# Blinkenlights.net
KiCad netlist of a schematic drawn in EAGLE
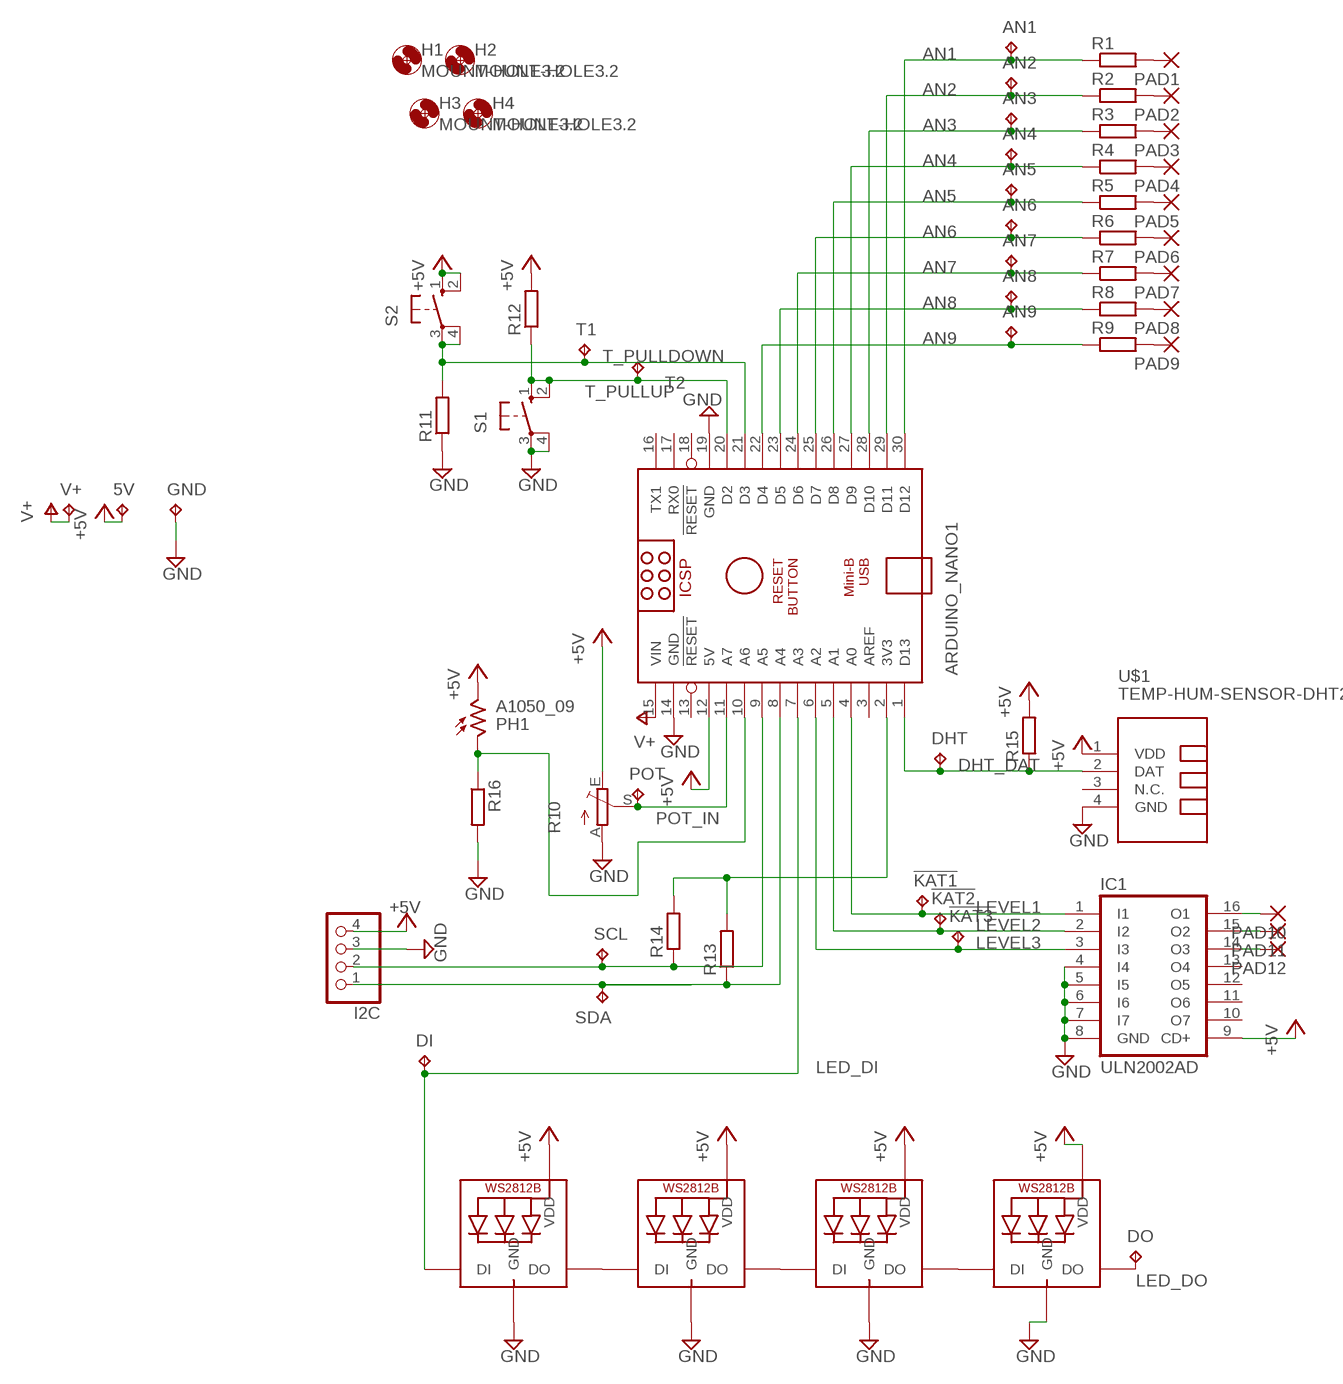
[diagram p0: schematic, sheet 1]

(export (version "E")
  (design (tool "Eeschema 10.0.6"))
  (components
    (comp (ref "!KAT1")
      (value "TPB1,27")
      (footprint "eagle-import:B1,27")
      (libsource (lib "eagle-import") (part "TPB1,27"))
    )
    (comp (ref "!KAT2")
      (value "TPB1,27")
      (footprint "eagle-import:B1,27")
      (libsource (lib "eagle-import") (part "TPB1,27"))
    )
    (comp (ref "!KAT3")
      (value "TPB1,27")
      (footprint "eagle-import:B1,27")
      (libsource (lib "eagle-import") (part "TPB1,27"))
    )
    (comp (ref "5V")
      (value "TPPAD1-17")
      (footprint "eagle-import:P1-17")
      (libsource (lib "eagle-import") (part "TPPAD1-17"))
    )
    (comp (ref "AN1")
      (value "TPB1,27")
      (footprint "eagle-import:B1,27")
      (libsource (lib "eagle-import") (part "TPB1,27"))
    )
    (comp (ref "AN2")
      (value "TPB1,27")
      (footprint "eagle-import:B1,27")
      (libsource (lib "eagle-import") (part "TPB1,27"))
    )
    (comp (ref "AN3")
      (value "TPB1,27")
      (footprint "eagle-import:B1,27")
      (libsource (lib "eagle-import") (part "TPB1,27"))
    )
    (comp (ref "AN4")
      (value "TPB1,27")
      (footprint "eagle-import:B1,27")
      (libsource (lib "eagle-import") (part "TPB1,27"))
    )
    (comp (ref "AN5")
      (value "TPB1,27")
      (footprint "eagle-import:B1,27")
      (libsource (lib "eagle-import") (part "TPB1,27"))
    )
    (comp (ref "AN6")
      (value "TPB1,27")
      (footprint "eagle-import:B1,27")
      (libsource (lib "eagle-import") (part "TPB1,27"))
    )
    (comp (ref "AN7")
      (value "TPB1,27")
      (footprint "eagle-import:B1,27")
      (libsource (lib "eagle-import") (part "TPB1,27"))
    )
    (comp (ref "AN8")
      (value "TPB1,27")
      (footprint "eagle-import:B1,27")
      (libsource (lib "eagle-import") (part "TPB1,27"))
    )
    (comp (ref "AN9")
      (value "TPB1,27")
      (footprint "eagle-import:B1,27")
      (libsource (lib "eagle-import") (part "TPB1,27"))
    )
    (comp (ref "ARDUINO_NANO1")
      (value "ARDUINO_NANO")
      (footprint "eagle-import:ARDUINO_NANO")
      (libsource (lib "eagle-import") (part "ARDUINO_NANO"))
    )
    (comp (ref "DHT")
      (value "TPB1,27")
      (footprint "eagle-import:B1,27")
      (libsource (lib "eagle-import") (part "TPB1,27"))
    )
    (comp (ref "DI")
      (value "TPB1,27")
      (footprint "eagle-import:B1,27")
      (libsource (lib "eagle-import") (part "TPB1,27"))
    )
    (comp (ref "DO")
      (value "TPB1,27")
      (footprint "eagle-import:B1,27")
      (libsource (lib "eagle-import") (part "TPB1,27"))
    )
    (comp (ref "GND")
      (value "TPPAD1-17")
      (footprint "eagle-import:P1-17")
      (libsource (lib "eagle-import") (part "TPPAD1-17"))
    )
    (comp (ref "H1")
      (value "MOUNT-HOLE3.2")
      (footprint "eagle-import:3,2")
      (libsource (lib "eagle-import") (part "MOUNT-HOLE3.2"))
    )
    (comp (ref "H2")
      (value "MOUNT-HOLE3.2")
      (footprint "eagle-import:3,2")
      (libsource (lib "eagle-import") (part "MOUNT-HOLE3.2"))
    )
    (comp (ref "H3")
      (value "MOUNT-HOLE3.2")
      (footprint "eagle-import:3,2")
      (libsource (lib "eagle-import") (part "MOUNT-HOLE3.2"))
    )
    (comp (ref "H4")
      (value "MOUNT-HOLE3.2")
      (footprint "eagle-import:3,2")
      (libsource (lib "eagle-import") (part "MOUNT-HOLE3.2"))
    )
    (comp (ref "I2C")
      (value "PINHD-1X4")
      (footprint "eagle-import:1X04")
      (libsource (lib "eagle-import") (part "PINHD-1X4"))
    )
    (comp (ref "IC1")
      (value "ULN2002AD")
      (footprint "eagle-import:SO16")
      (libsource (lib "eagle-import") (part "ULN2002AD"))
    )
    (comp (ref "LED1")
      (value "WS2812B5050")
      (footprint "eagle-import:WS2812B")
      (libsource (lib "eagle-import") (part "WS2812B5050"))
    )
    (comp (ref "LED2")
      (value "WS2812B5050")
      (footprint "eagle-import:WS2812B")
      (libsource (lib "eagle-import") (part "WS2812B5050"))
    )
    (comp (ref "LED3")
      (value "WS2812B5050")
      (footprint "eagle-import:WS2812B")
      (libsource (lib "eagle-import") (part "WS2812B5050"))
    )
    (comp (ref "LED4")
      (value "WS2812B5050")
      (footprint "eagle-import:WS2812B")
      (libsource (lib "eagle-import") (part "WS2812B5050"))
    )
    (comp (ref "PAD1")
      (value "2,54/1,1")
      (footprint "eagle-import:2,54_1,1")
      (libsource (lib "eagle-import") (part "2,54/1,1"))
    )
    (comp (ref "PAD2")
      (value "2,54/1,1")
      (footprint "eagle-import:2,54_1,1")
      (libsource (lib "eagle-import") (part "2,54/1,1"))
    )
    (comp (ref "PAD3")
      (value "2,54/1,1")
      (footprint "eagle-import:2,54_1,1")
      (libsource (lib "eagle-import") (part "2,54/1,1"))
    )
    (comp (ref "PAD4")
      (value "2,54/1,1")
      (footprint "eagle-import:2,54_1,1")
      (libsource (lib "eagle-import") (part "2,54/1,1"))
    )
    (comp (ref "PAD5")
      (value "2,54/1,1")
      (footprint "eagle-import:2,54_1,1")
      (libsource (lib "eagle-import") (part "2,54/1,1"))
    )
    (comp (ref "PAD6")
      (value "2,54/1,1")
      (footprint "eagle-import:2,54_1,1")
      (libsource (lib "eagle-import") (part "2,54/1,1"))
    )
    (comp (ref "PAD7")
      (value "2,54/1,1")
      (footprint "eagle-import:2,54_1,1")
      (libsource (lib "eagle-import") (part "2,54/1,1"))
    )
    (comp (ref "PAD8")
      (value "2,54/1,1")
      (footprint "eagle-import:2,54_1,1")
      (libsource (lib "eagle-import") (part "2,54/1,1"))
    )
    (comp (ref "PAD9")
      (value "2,54/1,1")
      (footprint "eagle-import:2,54_1,1")
      (libsource (lib "eagle-import") (part "2,54/1,1"))
    )
    (comp (ref "PAD10")
      (value "2,54/1,1")
      (footprint "eagle-import:2,54_1,1")
      (libsource (lib "eagle-import") (part "2,54/1,1"))
    )
    (comp (ref "PAD11")
      (value "2,54/1,1")
      (footprint "eagle-import:2,54_1,1")
      (libsource (lib "eagle-import") (part "2,54/1,1"))
    )
    (comp (ref "PAD12")
      (value "2,54/1,1")
      (footprint "eagle-import:2,54_1,1")
      (libsource (lib "eagle-import") (part "2,54/1,1"))
    )
    (comp (ref "PH1")
      (value "A1050_09")
      (footprint "eagle-import:T0-46-A10XX")
      (libsource (lib "eagle-import") (part "A1050_09"))
    )
    (comp (ref "POT")
      (value "TPB1,27")
      (footprint "eagle-import:B1,27")
      (libsource (lib "eagle-import") (part "TPB1,27"))
    )
    (comp (ref "R1")
      (value "R-EU_R0603")
      (footprint "eagle-import:R0603")
      (libsource (lib "eagle-import") (part "R-EU_R0603"))
    )
    (comp (ref "R2")
      (value "R-EU_R0603")
      (footprint "eagle-import:R0603")
      (libsource (lib "eagle-import") (part "R-EU_R0603"))
    )
    (comp (ref "R3")
      (value "R-EU_R0603")
      (footprint "eagle-import:R0603")
      (libsource (lib "eagle-import") (part "R-EU_R0603"))
    )
    (comp (ref "R4")
      (value "R-EU_R0603")
      (footprint "eagle-import:R0603")
      (libsource (lib "eagle-import") (part "R-EU_R0603"))
    )
    (comp (ref "R5")
      (value "R-EU_R0603")
      (footprint "eagle-import:R0603")
      (libsource (lib "eagle-import") (part "R-EU_R0603"))
    )
    (comp (ref "R6")
      (value "R-EU_R0603")
      (footprint "eagle-import:R0603")
      (libsource (lib "eagle-import") (part "R-EU_R0603"))
    )
    (comp (ref "R7")
      (value "R-EU_R0603")
      (footprint "eagle-import:R0603")
      (libsource (lib "eagle-import") (part "R-EU_R0603"))
    )
    (comp (ref "R8")
      (value "R-EU_R0603")
      (footprint "eagle-import:R0603")
      (libsource (lib "eagle-import") (part "R-EU_R0603"))
    )
    (comp (ref "R9")
      (value "R-EU_R0603")
      (footprint "eagle-import:R0603")
      (libsource (lib "eagle-import") (part "R-EU_R0603"))
    )
    (comp (ref "R10")
      (value "TRIM_EU-RJ9W")
      (footprint "eagle-import:RJ9W")
      (libsource (lib "eagle-import") (part "TRIM_EU-RJ9W"))
    )
    (comp (ref "R11")
      (value "R-EU_R0805")
      (footprint "eagle-import:R0805")
      (libsource (lib "eagle-import") (part "R-EU_R0805"))
    )
    (comp (ref "R12")
      (value "R-EU_R0805")
      (footprint "eagle-import:R0805")
      (libsource (lib "eagle-import") (part "R-EU_R0805"))
    )
    (comp (ref "R13")
      (value "R-EU_R0805")
      (footprint "eagle-import:R0805")
      (libsource (lib "eagle-import") (part "R-EU_R0805"))
    )
    (comp (ref "R14")
      (value "R-EU_R0805")
      (footprint "eagle-import:R0805")
      (libsource (lib "eagle-import") (part "R-EU_R0805"))
    )
    (comp (ref "R15")
      (value "R-EU_R0805")
      (footprint "eagle-import:R0805")
      (libsource (lib "eagle-import") (part "R-EU_R0805"))
    )
    (comp (ref "R16")
      (value "R-EU_R0805")
      (footprint "eagle-import:R0805")
      (libsource (lib "eagle-import") (part "R-EU_R0805"))
    )
    (comp (ref "S1")
      (value "10-XX")
      (footprint "eagle-import:B3F-10XX")
      (fields (field (name "MPN") "B3F-1000"))
      (libsource (lib "eagle-import") (part "10-XX"))
    )
    (comp (ref "S2")
      (value "10-XX")
      (footprint "eagle-import:B3F-10XX")
      (fields (field (name "MPN") "B3F-1000"))
      (libsource (lib "eagle-import") (part "10-XX"))
    )
    (comp (ref "SCL")
      (value "TPB1,27")
      (footprint "eagle-import:B1,27")
      (libsource (lib "eagle-import") (part "TPB1,27"))
    )
    (comp (ref "SDA")
      (value "TPB1,27")
      (footprint "eagle-import:B1,27")
      (libsource (lib "eagle-import") (part "TPB1,27"))
    )
    (comp (ref "T1")
      (value "TPB1,27")
      (footprint "eagle-import:B1,27")
      (libsource (lib "eagle-import") (part "TPB1,27"))
    )
    (comp (ref "T2")
      (value "TPB1,27")
      (footprint "eagle-import:B1,27")
      (libsource (lib "eagle-import") (part "TPB1,27"))
    )
    (comp (ref "U$1")
      (value "TEMP-HUM-SENSOR-DHT22")
      (footprint "eagle-import:TEMP-HUM-SENSOR-DHT22")
      (libsource (lib "eagle-import") (part "TEMP-HUM-SENSOR-DHT22"))
    )
    (comp (ref "V+")
      (value "TPPAD1-17")
      (footprint "eagle-import:P1-17")
      (libsource (lib "eagle-import") (part "TPPAD1-17"))
    )
  )
  (nets
    (net (code "1") (name "+5V") (class "Default")
      (node (ref "5V") (pin "TP") (pinfunction "TP_TP") (pintype "input"))
      (node (ref "ARDUINO_NANO1") (pin "12") (pinfunction "5V_12") (pintype "power_in"))
      (node (ref "I2C") (pin "4") (pinfunction "4_4") (pintype "passive"))
      (node (ref "IC1") (pin "9") (pinfunction "CD+_9") (pintype "passive"))
      (node (ref "LED1") (pin "1-VDD") (pinfunction "VDD_1-VDD") (pintype "power_in"))
      (node (ref "LED2") (pin "1-VDD") (pinfunction "VDD_1-VDD") (pintype "power_in"))
      (node (ref "LED3") (pin "1-VDD") (pinfunction "VDD_1-VDD") (pintype "power_in"))
      (node (ref "LED4") (pin "1-VDD") (pinfunction "VDD_1-VDD") (pintype "power_in"))
      (node (ref "PH1") (pin "2") (pinfunction "2_2") (pintype "passive"))
      (node (ref "R10") (pin "E") (pinfunction "E_E") (pintype "passive"))
      (node (ref "R12") (pin "2") (pinfunction "2_2") (pintype "passive"))
      (node (ref "R15") (pin "2") (pinfunction "2_2") (pintype "passive"))
      (node (ref "S2") (pin "1") (pinfunction "S_1") (pintype "passive"))
      (node (ref "S2") (pin "2") (pinfunction "S1_2") (pintype "passive"))
      (node (ref "U$1") (pin "1") (pinfunction "VDD_1") (pintype "power_in"))
    )
    (net (code "2") (name "/AN1") (class "Default")
      (node (ref "AN1") (pin "TP") (pinfunction "TP_TP") (pintype "input"))
      (node (ref "ARDUINO_NANO1") (pin "30") (pinfunction "D12_30") (pintype "bidirectional"))
      (node (ref "R1") (pin "1") (pinfunction "1_1") (pintype "passive"))
    )
    (net (code "3") (name "/AN2") (class "Default")
      (node (ref "AN2") (pin "TP") (pinfunction "TP_TP") (pintype "input"))
      (node (ref "ARDUINO_NANO1") (pin "29") (pinfunction "D11_29") (pintype "bidirectional"))
      (node (ref "R2") (pin "1") (pinfunction "1_1") (pintype "passive"))
    )
    (net (code "4") (name "/AN3") (class "Default")
      (node (ref "AN3") (pin "TP") (pinfunction "TP_TP") (pintype "input"))
      (node (ref "ARDUINO_NANO1") (pin "28") (pinfunction "D10_28") (pintype "bidirectional"))
      (node (ref "R3") (pin "1") (pinfunction "1_1") (pintype "passive"))
    )
    (net (code "5") (name "/AN4") (class "Default")
      (node (ref "AN4") (pin "TP") (pinfunction "TP_TP") (pintype "input"))
      (node (ref "ARDUINO_NANO1") (pin "27") (pinfunction "D9_27") (pintype "bidirectional"))
      (node (ref "R4") (pin "1") (pinfunction "1_1") (pintype "passive"))
    )
    (net (code "6") (name "/AN5") (class "Default")
      (node (ref "AN5") (pin "TP") (pinfunction "TP_TP") (pintype "input"))
      (node (ref "ARDUINO_NANO1") (pin "26") (pinfunction "D8_26") (pintype "bidirectional"))
      (node (ref "R5") (pin "1") (pinfunction "1_1") (pintype "passive"))
    )
    (net (code "7") (name "/AN6") (class "Default")
      (node (ref "AN6") (pin "TP") (pinfunction "TP_TP") (pintype "input"))
      (node (ref "ARDUINO_NANO1") (pin "25") (pinfunction "D7_25") (pintype "bidirectional"))
      (node (ref "R6") (pin "1") (pinfunction "1_1") (pintype "passive"))
    )
    (net (code "8") (name "/AN7") (class "Default")
      (node (ref "AN7") (pin "TP") (pinfunction "TP_TP") (pintype "input"))
      (node (ref "ARDUINO_NANO1") (pin "24") (pinfunction "D6_24") (pintype "bidirectional"))
      (node (ref "R7") (pin "1") (pinfunction "1_1") (pintype "passive"))
    )
    (net (code "9") (name "/AN8") (class "Default")
      (node (ref "AN8") (pin "TP") (pinfunction "TP_TP") (pintype "input"))
      (node (ref "ARDUINO_NANO1") (pin "23") (pinfunction "D5_23") (pintype "bidirectional"))
      (node (ref "R8") (pin "1") (pinfunction "1_1") (pintype "passive"))
    )
    (net (code "10") (name "/AN9") (class "Default")
      (node (ref "AN9") (pin "TP") (pinfunction "TP_TP") (pintype "input"))
      (node (ref "ARDUINO_NANO1") (pin "22") (pinfunction "D4_22") (pintype "bidirectional"))
      (node (ref "R9") (pin "1") (pinfunction "1_1") (pintype "passive"))
    )
    (net (code "11") (name "/DHT_DAT") (class "Default")
      (node (ref "ARDUINO_NANO1") (pin "1") (pinfunction "D13_1") (pintype "bidirectional"))
      (node (ref "DHT") (pin "TP") (pinfunction "TP_TP") (pintype "input"))
      (node (ref "R15") (pin "1") (pinfunction "1_1") (pintype "passive"))
      (node (ref "U$1") (pin "2") (pinfunction "DAT_2") (pintype "bidirectional"))
    )
    (net (code "12") (name "/LED_DI") (class "Default")
      (node (ref "ARDUINO_NANO1") (pin "7") (pinfunction "A3_7") (pintype "bidirectional"))
      (node (ref "DI") (pin "TP") (pinfunction "TP_TP") (pintype "input"))
      (node (ref "LED1") (pin "4-DIN") (pinfunction "DI_4-DIN") (pintype "input"))
    )
    (net (code "14") (name "/LED_DO") (class "Default")
      (node (ref "DO") (pin "TP") (pinfunction "TP_TP") (pintype "input"))
      (node (ref "LED4") (pin "2-DOUT") (pinfunction "DO_2-DOUT") (pintype "output"))
    )
    (net (code "15") (name "/LEVEL1") (class "Default")
      (node (ref "!KAT1") (pin "TP") (pinfunction "TP_TP") (pintype "input"))
      (node (ref "ARDUINO_NANO1") (pin "4") (pinfunction "A0_4") (pintype "bidirectional"))
      (node (ref "IC1") (pin "1") (pinfunction "I1_1") (pintype "input"))
    )
    (net (code "16") (name "/LEVEL2") (class "Default")
      (node (ref "!KAT2") (pin "TP") (pinfunction "TP_TP") (pintype "input"))
      (node (ref "ARDUINO_NANO1") (pin "5") (pinfunction "A1_5") (pintype "bidirectional"))
      (node (ref "IC1") (pin "2") (pinfunction "I2_2") (pintype "input"))
    )
    (net (code "17") (name "/LEVEL3") (class "Default")
      (node (ref "!KAT3") (pin "TP") (pinfunction "TP_TP") (pintype "input"))
      (node (ref "ARDUINO_NANO1") (pin "6") (pinfunction "A2_6") (pintype "bidirectional"))
      (node (ref "IC1") (pin "3") (pinfunction "I3_3") (pintype "input"))
    )
    (net (code "18") (name "/POT_IN") (class "Default")
      (node (ref "ARDUINO_NANO1") (pin "11") (pinfunction "A7_11") (pintype "bidirectional"))
      (node (ref "POT") (pin "TP") (pinfunction "TP_TP") (pintype "input"))
      (node (ref "R10") (pin "S") (pinfunction "S_S") (pintype "passive"))
    )
    (net (code "19") (name "/T_PULLDOWN") (class "Default")
      (node (ref "ARDUINO_NANO1") (pin "21") (pinfunction "D3_21") (pintype "bidirectional"))
      (node (ref "R11") (pin "2") (pinfunction "2_2") (pintype "passive"))
      (node (ref "S2") (pin "3") (pinfunction "P_3") (pintype "passive"))
      (node (ref "S2") (pin "4") (pinfunction "P1_4") (pintype "passive"))
      (node (ref "T1") (pin "TP") (pinfunction "TP_TP") (pintype "input"))
    )
    (net (code "20") (name "/T_PULLUP") (class "Default")
      (node (ref "ARDUINO_NANO1") (pin "20") (pinfunction "D2_20") (pintype "bidirectional"))
      (node (ref "R12") (pin "1") (pinfunction "1_1") (pintype "passive"))
      (node (ref "S1") (pin "1") (pinfunction "S_1") (pintype "passive"))
      (node (ref "S1") (pin "2") (pinfunction "S1_2") (pintype "passive"))
      (node (ref "T2") (pin "TP") (pinfunction "TP_TP") (pintype "input"))
    )
    (net (code "21") (name "GND") (class "Default")
      (node (ref "ARDUINO_NANO1") (pin "14") (pinfunction "GND_14") (pintype "power_in"))
      (node (ref "ARDUINO_NANO1") (pin "19") (pinfunction "GND_19") (pintype "power_in"))
      (node (ref "GND") (pin "TP") (pinfunction "TP_TP") (pintype "input"))
      (node (ref "I2C") (pin "3") (pinfunction "3_3") (pintype "passive"))
      (node (ref "IC1") (pin "4") (pinfunction "I4_4") (pintype "input"))
      (node (ref "IC1") (pin "5") (pinfunction "I5_5") (pintype "input"))
      (node (ref "IC1") (pin "6") (pinfunction "I6_6") (pintype "input"))
      (node (ref "IC1") (pin "7") (pinfunction "I7_7") (pintype "input"))
      (node (ref "IC1") (pin "8") (pinfunction "GND_8") (pintype "power_in"))
      (node (ref "LED1") (pin "3-GND") (pinfunction "GND_3-GND") (pintype "power_in"))
      (node (ref "LED2") (pin "3-GND") (pinfunction "GND_3-GND") (pintype "power_in"))
      (node (ref "LED3") (pin "3-GND") (pinfunction "GND_3-GND") (pintype "power_in"))
      (node (ref "LED4") (pin "3-GND") (pinfunction "GND_3-GND") (pintype "power_in"))
      (node (ref "R10") (pin "A") (pinfunction "A_A") (pintype "passive"))
      (node (ref "R11") (pin "1") (pinfunction "1_1") (pintype "passive"))
      (node (ref "R16") (pin "2") (pinfunction "2_2") (pintype "passive"))
      (node (ref "S1") (pin "3") (pinfunction "P_3") (pintype "passive"))
      (node (ref "S1") (pin "4") (pinfunction "P1_4") (pintype "passive"))
      (node (ref "U$1") (pin "4") (pinfunction "GND_4") (pintype "power_in"))
    )
    (net (code "22") (name "Net-(ARDUINO_NANO1-3V3)") (class "Default")
      (node (ref "ARDUINO_NANO1") (pin "2") (pinfunction "3V3_2") (pintype "output"))
      (node (ref "R13") (pin "2") (pinfunction "2_2") (pintype "passive"))
      (node (ref "R14") (pin "2") (pinfunction "2_2") (pintype "passive"))
    )
    (net (code "23") (name "Net-(ARDUINO_NANO1-A4)") (class "Default")
      (node (ref "ARDUINO_NANO1") (pin "8") (pinfunction "A4_8") (pintype "bidirectional"))
      (node (ref "I2C") (pin "1") (pinfunction "1_1") (pintype "passive"))
      (node (ref "R13") (pin "1") (pinfunction "1_1") (pintype "passive"))
      (node (ref "SDA") (pin "TP") (pinfunction "TP_TP") (pintype "input"))
    )
    (net (code "24") (name "Net-(ARDUINO_NANO1-A5)") (class "Default")
      (node (ref "ARDUINO_NANO1") (pin "9") (pinfunction "A5_9") (pintype "bidirectional"))
      (node (ref "I2C") (pin "2") (pinfunction "2_2") (pintype "passive"))
      (node (ref "R14") (pin "1") (pinfunction "1_1") (pintype "passive"))
      (node (ref "SCL") (pin "TP") (pinfunction "TP_TP") (pintype "input"))
    )
    (net (code "25") (name "Net-(ARDUINO_NANO1-A6)") (class "Default")
      (node (ref "ARDUINO_NANO1") (pin "10") (pinfunction "A6_10") (pintype "bidirectional"))
      (node (ref "PH1") (pin "1") (pinfunction "1_1") (pintype "passive"))
      (node (ref "R16") (pin "1") (pinfunction "1_1") (pintype "passive"))
    )
    (net (code "26") (name "Net-(IC1-O1)") (class "Default")
      (node (ref "IC1") (pin "16") (pinfunction "O1_16") (pintype "open_collector"))
      (node (ref "PAD10") (pin "1") (pinfunction "P_1") (pintype "passive"))
    )
    (net (code "27") (name "Net-(IC1-O2)") (class "Default")
      (node (ref "IC1") (pin "15") (pinfunction "O2_15") (pintype "open_collector"))
      (node (ref "PAD11") (pin "1") (pinfunction "P_1") (pintype "passive"))
    )
    (net (code "28") (name "Net-(IC1-O3)") (class "Default")
      (node (ref "IC1") (pin "14") (pinfunction "O3_14") (pintype "open_collector"))
      (node (ref "PAD12") (pin "1") (pinfunction "P_1") (pintype "passive"))
    )
    (net (code "29") (name "Net-(LED1-DO)") (class "Default")
      (node (ref "LED1") (pin "2-DOUT") (pinfunction "DO_2-DOUT") (pintype "output"))
      (node (ref "LED2") (pin "4-DIN") (pinfunction "DI_4-DIN") (pintype "input"))
    )
    (net (code "30") (name "Net-(LED2-DO)") (class "Default")
      (node (ref "LED2") (pin "2-DOUT") (pinfunction "DO_2-DOUT") (pintype "output"))
      (node (ref "LED3") (pin "4-DIN") (pinfunction "DI_4-DIN") (pintype "input"))
    )
    (net (code "31") (name "Net-(LED3-DO)") (class "Default")
      (node (ref "LED3") (pin "2-DOUT") (pinfunction "DO_2-DOUT") (pintype "output"))
      (node (ref "LED4") (pin "4-DIN") (pinfunction "DI_4-DIN") (pintype "input"))
    )
    (net (code "32") (name "Net-(PAD1-P)") (class "Default")
      (node (ref "PAD1") (pin "1") (pinfunction "P_1") (pintype "passive"))
      (node (ref "R1") (pin "2") (pinfunction "2_2") (pintype "passive"))
    )
    (net (code "33") (name "Net-(PAD2-P)") (class "Default")
      (node (ref "PAD2") (pin "1") (pinfunction "P_1") (pintype "passive"))
      (node (ref "R2") (pin "2") (pinfunction "2_2") (pintype "passive"))
    )
    (net (code "34") (name "Net-(PAD3-P)") (class "Default")
      (node (ref "PAD3") (pin "1") (pinfunction "P_1") (pintype "passive"))
      (node (ref "R3") (pin "2") (pinfunction "2_2") (pintype "passive"))
    )
    (net (code "35") (name "Net-(PAD4-P)") (class "Default")
      (node (ref "PAD4") (pin "1") (pinfunction "P_1") (pintype "passive"))
      (node (ref "R4") (pin "2") (pinfunction "2_2") (pintype "passive"))
    )
    (net (code "36") (name "Net-(PAD5-P)") (class "Default")
      (node (ref "PAD5") (pin "1") (pinfunction "P_1") (pintype "passive"))
      (node (ref "R5") (pin "2") (pinfunction "2_2") (pintype "passive"))
    )
    (net (code "37") (name "Net-(PAD6-P)") (class "Default")
      (node (ref "PAD6") (pin "1") (pinfunction "P_1") (pintype "passive"))
      (node (ref "R6") (pin "2") (pinfunction "2_2") (pintype "passive"))
    )
    (net (code "38") (name "Net-(PAD7-P)") (class "Default")
      (node (ref "PAD7") (pin "1") (pinfunction "P_1") (pintype "passive"))
      (node (ref "R7") (pin "2") (pinfunction "2_2") (pintype "passive"))
    )
    (net (code "39") (name "Net-(PAD8-P)") (class "Default")
      (node (ref "PAD8") (pin "1") (pinfunction "P_1") (pintype "passive"))
      (node (ref "R8") (pin "2") (pinfunction "2_2") (pintype "passive"))
    )
    (net (code "40") (name "Net-(PAD9-P)") (class "Default")
      (node (ref "PAD9") (pin "1") (pinfunction "P_1") (pintype "passive"))
      (node (ref "R9") (pin "2") (pinfunction "2_2") (pintype "passive"))
    )
    (net (code "41") (name "V+") (class "Default")
      (node (ref "ARDUINO_NANO1") (pin "15") (pinfunction "VIN_15") (pintype "power_in"))
      (node (ref "V+") (pin "TP") (pinfunction "TP_TP") (pintype "input"))
    )
    (net (code "42") (name "unconnected-(ARDUINO_NANO1-AREF-Pad3)") (class "Default")
      (node (ref "ARDUINO_NANO1") (pin "3") (pinfunction "AREF_3") (pintype "input"))
    )
    (net (code "43") (name "unconnected-(ARDUINO_NANO1-RX0-Pad17)") (class "Default")
      (node (ref "ARDUINO_NANO1") (pin "17") (pinfunction "RX0_17") (pintype "bidirectional"))
    )
    (net (code "44") (name "unconnected-(ARDUINO_NANO1-TX1-Pad16)") (class "Default")
      (node (ref "ARDUINO_NANO1") (pin "16") (pinfunction "TX1_16") (pintype "bidirectional"))
    )
    (net (code "45") (name "unconnected-(ARDUINO_NANO1-~{RESET}-Pad13)") (class "Default")
      (node (ref "ARDUINO_NANO1") (pin "13") (pinfunction "~{RESET}_13") (pintype "input"))
    )
    (net (code "46") (name "unconnected-(ARDUINO_NANO1-~{RESET}-Pad18)") (class "Default")
      (node (ref "ARDUINO_NANO1") (pin "18") (pinfunction "~{RESET}_18") (pintype "input"))
    )
    (net (code "47") (name "unconnected-(IC1-O4-Pad13)") (class "Default")
      (node (ref "IC1") (pin "13") (pinfunction "O4_13") (pintype "open_collector"))
    )
    (net (code "48") (name "unconnected-(IC1-O5-Pad12)") (class "Default")
      (node (ref "IC1") (pin "12") (pinfunction "O5_12") (pintype "open_collector"))
    )
    (net (code "49") (name "unconnected-(IC1-O6-Pad11)") (class "Default")
      (node (ref "IC1") (pin "11") (pinfunction "O6_11") (pintype "open_collector"))
    )
    (net (code "50") (name "unconnected-(IC1-O7-Pad10)") (class "Default")
      (node (ref "IC1") (pin "10") (pinfunction "O7_10") (pintype "open_collector"))
    )
    (net (code "51") (name "unconnected-(U$1-N.C.-Pad3)") (class "Default")
      (node (ref "U$1") (pin "3") (pinfunction "N.C._3") (pintype "passive"))
    )
  )
)
